# JTAG.net
KiCad netlist of a schematic drawn in Altium Designer
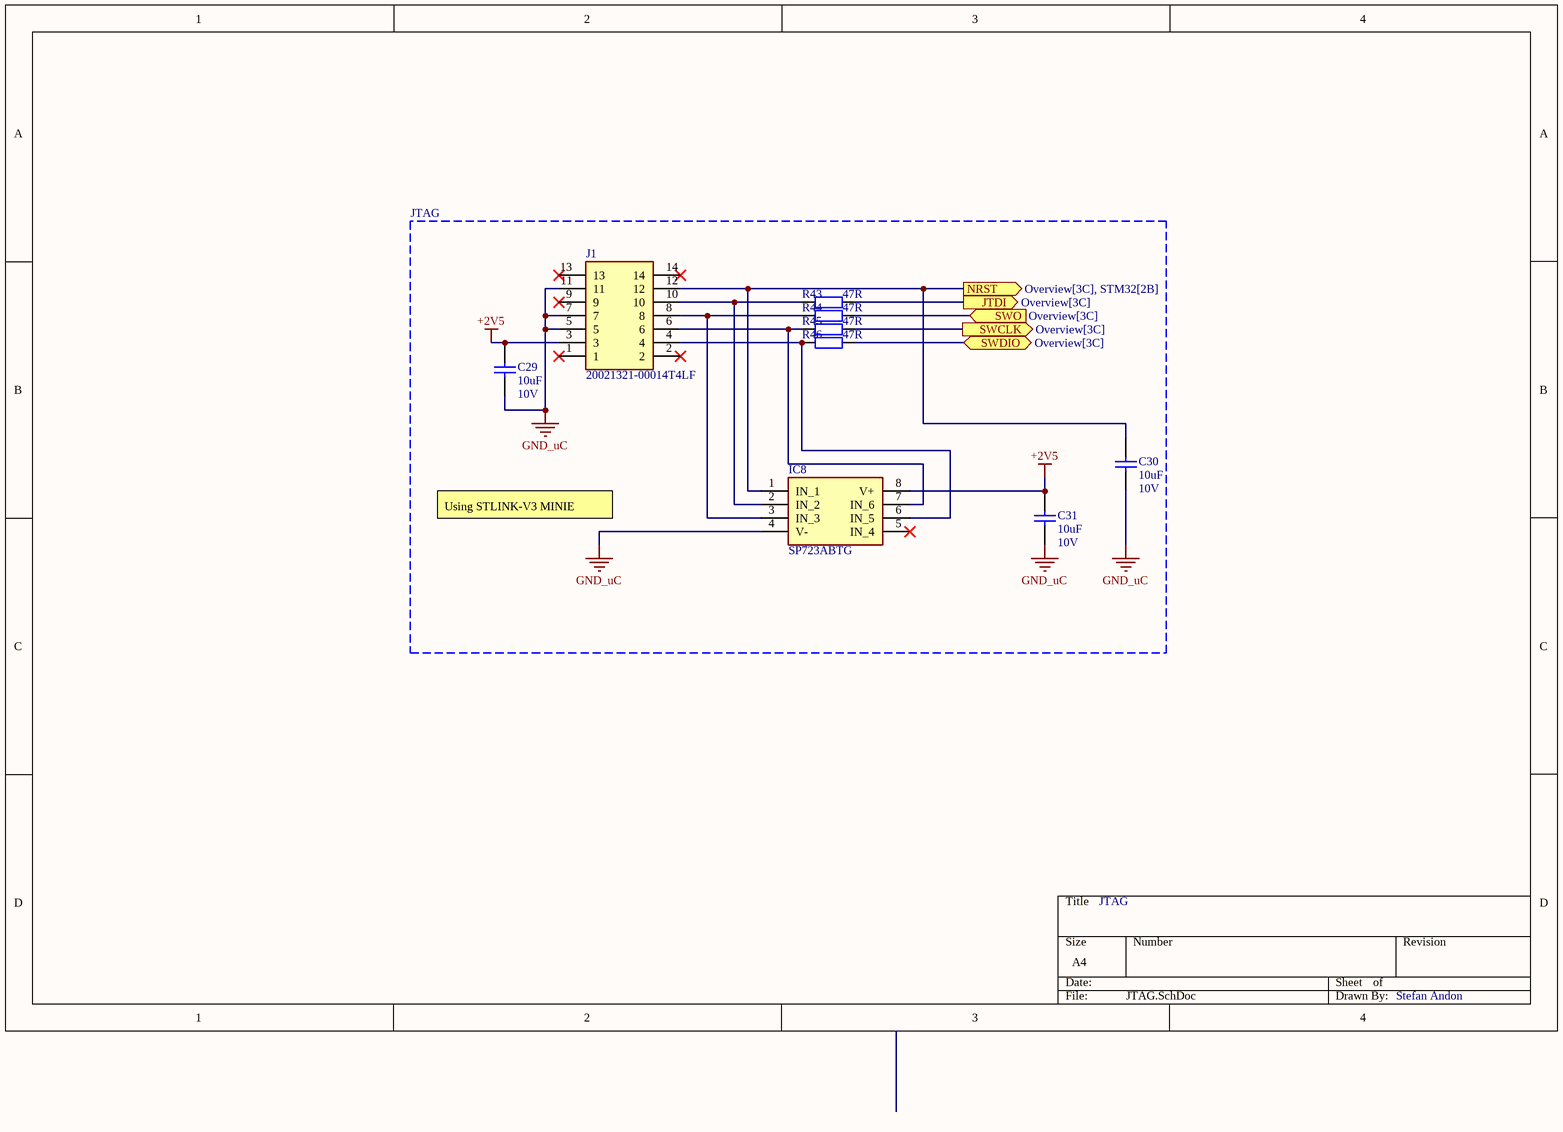
[diagram p0: JTAG.SchDoc]

(export (version "E")
  (design (tool "Eeschema 10.0.6"))
  (components
    (comp (ref "C29")
      (value "10uF")
      (footprint "CAP_0603")
      (description "SMD Capacitor")
      (fields
        (field (name "TOLERANCE") "tbd")
        (field (name "VOLTAGE") "10V")
        (field (name "Comment") "Capacitor_SMD")
      )
      (libsource (lib "TUfast e") (part "SMD Capacitor"))
    )
    (comp (ref "C30")
      (value "10uF")
      (footprint "CAP_0603")
      (description "SMD Capacitor")
      (fields
        (field (name "TOLERANCE") "tbd")
        (field (name "VOLTAGE") "10V")
        (field (name "Comment") "Capacitor_SMD")
      )
      (libsource (lib "TUfast e") (part "SMD Capacitor"))
    )
    (comp (ref "C31")
      (value "10uF")
      (footprint "CAP_0603")
      (description "SMD Capacitor")
      (fields
        (field (name "TOLERANCE") "tbd")
        (field (name "VOLTAGE") "10V")
        (field (name "Comment") "Capacitor_SMD")
      )
      (libsource (lib "TUfast e") (part "SMD Capacitor"))
    )
    (comp (ref "IC8")
      (value "SP723ABTG")
      (footprint "SamacSys:SOIC127P600X175-8N")
      (description "Integrated Circuit")
      (fields (field (name "MOUSER PART NUMBER") "576-SP723ABTG"))
      (libsource (lib "*") (part "SP723ABTG"))
    )
    (comp (ref "J1")
      (value "20021321-00014T4LF")
      (footprint "SamacSys:2002132100014T4LF")
      (description "Connector")
      (fields (field (name "MOUSER PART NUMBER") "649-221321-00014T4LF"))
      (libsource (lib "*") (part "20021321-00014T4LF"))
    )
    (comp (ref "R43")
      (value "47R")
      (footprint "RES_0603")
      (fields
        (field (name "TOLERANCE") "tbd")
        (field (name "POWER") "7W")
        (field (name "Comment") "Resistor_SMD")
      )
      (libsource (lib "TUfast e") (part "Resistor"))
    )
    (comp (ref "R44")
      (value "47R")
      (footprint "RES_0603")
      (fields
        (field (name "TOLERANCE") "tbd")
        (field (name "POWER") "7W")
        (field (name "Comment") "Resistor_SMD")
      )
      (libsource (lib "TUfast e") (part "Resistor"))
    )
    (comp (ref "R45")
      (value "47R")
      (footprint "RES_0603")
      (fields
        (field (name "TOLERANCE") "tbd")
        (field (name "POWER") "7W")
        (field (name "Comment") "Resistor_SMD")
      )
      (libsource (lib "TUfast e") (part "Resistor"))
    )
    (comp (ref "R46")
      (value "47R")
      (footprint "RES_0603")
      (fields
        (field (name "TOLERANCE") "tbd")
        (field (name "POWER") "7W")
        (field (name "Comment") "Resistor_SMD")
      )
      (libsource (lib "TUfast e") (part "Resistor"))
    )
  )
  (nets
    (net (code "1") (name "+2V5") (class "Default")
      (node (ref "C29") (pin "1") (pinfunction "1_1") (pintype "passive"))
      (node (ref "C31") (pin "1") (pinfunction "1_1") (pintype "passive"))
      (node (ref "IC8") (pin "8") (pinfunction "V+_8") (pintype "passive"))
      (node (ref "J1") (pin "3") (pinfunction "3_3") (pintype "passive"))
    )
    (net (code "2") (name "/JTDI") (class "Default")
      (node (ref "R43") (pin "1") (pinfunction "1_1") (pintype "passive"))
    )
    (net (code "3") (name "/NRST") (class "Default")
      (node (ref "C30") (pin "1") (pinfunction "1_1") (pintype "passive"))
      (node (ref "IC8") (pin "1") (pinfunction "IN_1_1") (pintype "passive"))
      (node (ref "J1") (pin "12") (pinfunction "12_12") (pintype "passive"))
    )
    (net (code "4") (name "/SWCLK") (class "Default")
      (node (ref "R45") (pin "1") (pinfunction "1_1") (pintype "passive"))
    )
    (net (code "5") (name "/SWDIO") (class "Default")
      (node (ref "R46") (pin "1") (pinfunction "1_1") (pintype "passive"))
    )
    (net (code "6") (name "/SWO") (class "Default")
      (node (ref "R44") (pin "1") (pinfunction "1_1") (pintype "passive"))
    )
    (net (code "7") (name "GND_uC") (class "Default")
      (node (ref "C29") (pin "2") (pinfunction "2_2") (pintype "passive"))
      (node (ref "C30") (pin "2") (pinfunction "2_2") (pintype "passive"))
      (node (ref "C31") (pin "2") (pinfunction "2_2") (pintype "passive"))
      (node (ref "IC8") (pin "4") (pinfunction "V-_4") (pintype "passive"))
      (node (ref "J1") (pin "11") (pinfunction "11_11") (pintype "passive"))
      (node (ref "J1") (pin "5") (pinfunction "5_5") (pintype "passive"))
      (node (ref "J1") (pin "7") (pinfunction "7_7") (pintype "passive"))
    )
    (net (code "8") (name "Net-(IC8-IN_2)") (class "Default")
      (node (ref "IC8") (pin "2") (pinfunction "IN_2_2") (pintype "passive"))
      (node (ref "J1") (pin "10") (pinfunction "10_10") (pintype "passive"))
      (node (ref "R43") (pin "2") (pinfunction "2_2") (pintype "passive"))
    )
    (net (code "9") (name "Net-(IC8-IN_3)") (class "Default")
      (node (ref "IC8") (pin "3") (pinfunction "IN_3_3") (pintype "passive"))
      (node (ref "J1") (pin "8") (pinfunction "8_8") (pintype "passive"))
      (node (ref "R44") (pin "2") (pinfunction "2_2") (pintype "passive"))
    )
    (net (code "10") (name "Net-(IC8-IN_5)") (class "Default")
      (node (ref "IC8") (pin "6") (pinfunction "IN_5_6") (pintype "passive"))
      (node (ref "J1") (pin "4") (pinfunction "4_4") (pintype "passive"))
      (node (ref "R46") (pin "2") (pinfunction "2_2") (pintype "passive"))
    )
    (net (code "11") (name "Net-(IC8-IN_6)") (class "Default")
      (node (ref "IC8") (pin "7") (pinfunction "IN_6_7") (pintype "passive"))
      (node (ref "J1") (pin "6") (pinfunction "6_6") (pintype "passive"))
      (node (ref "R45") (pin "2") (pinfunction "2_2") (pintype "passive"))
    )
    (net (code "12") (name "unconnected-(IC8-IN_4-Pad5)") (class "Default")
      (node (ref "IC8") (pin "5") (pinfunction "IN_4_5") (pintype "passive+no_connect"))
    )
    (net (code "13") (name "unconnected-(J1-Pad1)") (class "Default")
      (node (ref "J1") (pin "1") (pinfunction "1_1") (pintype "passive+no_connect"))
    )
    (net (code "14") (name "unconnected-(J1-Pad2)") (class "Default")
      (node (ref "J1") (pin "2") (pinfunction "2_2") (pintype "passive+no_connect"))
    )
    (net (code "15") (name "unconnected-(J1-Pad9)") (class "Default")
      (node (ref "J1") (pin "9") (pinfunction "9_9") (pintype "passive+no_connect"))
    )
    (net (code "16") (name "unconnected-(J1-Pad13)") (class "Default")
      (node (ref "J1") (pin "13") (pinfunction "13_13") (pintype "passive+no_connect"))
    )
    (net (code "17") (name "unconnected-(J1-Pad14)") (class "Default")
      (node (ref "J1") (pin "14") (pinfunction "14_14") (pintype "passive+no_connect"))
    )
  )
)
